# m20048_GPS.net
KiCad netlist of a schematic drawn in Altium Designer
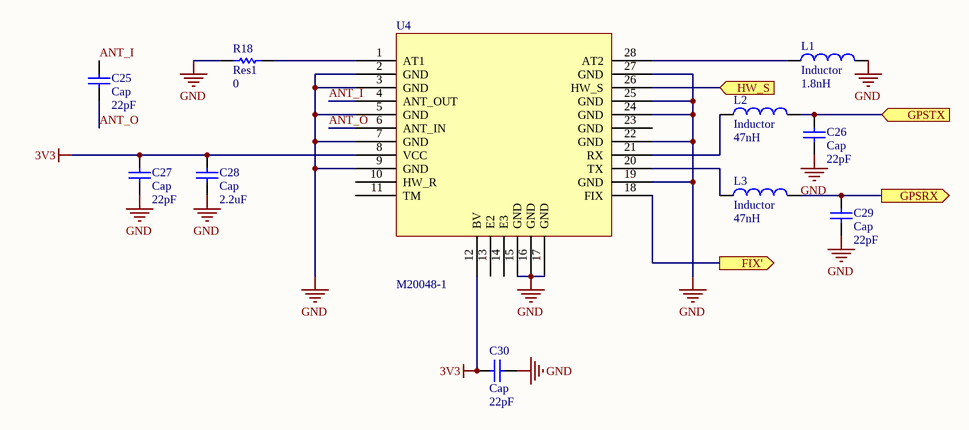
[diagram p0: m20048 GPS.SchDoc]

(export (version "E")
  (design (tool "Eeschema 10.0.6"))
  (components
    (comp (ref "C25")
      (value "Cap")
      (footprint "0402-A")
      (description "Capacitor")
      (fields (field (name "ALTIUM_VALUE") "22pF") (field (name "PUBLISHER") "Altium Limited"))
      (libsource (lib "Miscellaneous Devices") (part "Cap"))
    )
    (comp (ref "C26")
      (value "Cap")
      (footprint "0402-A")
      (description "Capacitor")
      (fields (field (name "ALTIUM_VALUE") "22pF") (field (name "PUBLISHER") "Altium Limited"))
      (libsource (lib "Miscellaneous Devices") (part "Cap"))
    )
    (comp (ref "C27")
      (value "Cap")
      (footprint "0402-A")
      (description "Capacitor")
      (fields (field (name "ALTIUM_VALUE") "22pF") (field (name "PUBLISHER") "Altium Limited"))
      (libsource (lib "Miscellaneous Devices") (part "Cap"))
    )
    (comp (ref "C28")
      (value "Cap")
      (footprint "0402-A")
      (description "Capacitor")
      (fields (field (name "ALTIUM_VALUE") "2.2uF") (field (name "PUBLISHER") "Altium Limited"))
      (libsource (lib "Miscellaneous Devices") (part "Cap"))
    )
    (comp (ref "C29")
      (value "Cap")
      (footprint "0402-A")
      (description "Capacitor")
      (fields (field (name "ALTIUM_VALUE") "22pF") (field (name "PUBLISHER") "Altium Limited"))
      (libsource (lib "Miscellaneous Devices") (part "Cap"))
    )
    (comp (ref "C30")
      (value "Cap")
      (footprint "0402-A")
      (description "Capacitor")
      (fields (field (name "ALTIUM_VALUE") "22pF") (field (name "PUBLISHER") "Altium Limited"))
      (libsource (lib "Miscellaneous Devices") (part "Cap"))
    )
    (comp (ref "L1")
      (value "Inductor")
      (footprint "0402-A")
      (fields (field (name "ALTIUM_VALUE") "1.8nH") (field (name "PUBLISHER") "Altium Limited"))
      (libsource (lib "Miscellaneous Devices") (part "Inductor"))
    )
    (comp (ref "L2")
      (value "Inductor")
      (footprint "0402-A")
      (fields (field (name "ALTIUM_VALUE") "47nH") (field (name "PUBLISHER") "Altium Limited"))
      (libsource (lib "Miscellaneous Devices") (part "Inductor"))
    )
    (comp (ref "L3")
      (value "Inductor")
      (footprint "0402-A")
      (fields (field (name "ALTIUM_VALUE") "47nH") (field (name "PUBLISHER") "Altium Limited"))
      (libsource (lib "Miscellaneous Devices") (part "Inductor"))
    )
    (comp (ref "R18")
      (value "Res1")
      (footprint "0402-A")
      (description "Resistor")
      (fields (field (name "ALTIUM_VALUE") "0") (field (name "PUBLISHER") "Altium Limited"))
      (libsource (lib "Miscellaneous Devices") (part "Res1"))
    )
    (comp (ref "U4") (value "M20048-1") (footprint "M20048-1") (libsource (lib "m20048") (part "M20048-1")))
  )
  (nets
    (net (code "1") (name "/ANT_I") (class "Default")
      (node (ref "C25") (pin "2") (pinfunction "2_2") (pintype "passive"))
      (node (ref "U4") (pin "4") (pinfunction "ANT_OUT_4") (pintype "passive"))
    )
    (net (code "2") (name "/ANT_O") (class "Default")
      (node (ref "C25") (pin "1") (pinfunction "1_1") (pintype "passive"))
      (node (ref "U4") (pin "6") (pinfunction "ANT_IN_6") (pintype "passive"))
    )
    (net (code "3") (name "/FIX'") (class "Default")
      (node (ref "U4") (pin "18") (pinfunction "FIX_18") (pintype "passive"))
    )
    (net (code "4") (name "/GPSRX") (class "Default")
      (node (ref "C29") (pin "2") (pinfunction "2_2") (pintype "passive"))
      (node (ref "L3") (pin "2") (pinfunction "2_2") (pintype "passive"))
    )
    (net (code "5") (name "/GPSTX") (class "Default")
      (node (ref "C26") (pin "2") (pinfunction "2_2") (pintype "passive"))
      (node (ref "L2") (pin "2") (pinfunction "2_2") (pintype "passive"))
    )
    (net (code "6") (name "/HW_S") (class "Default")
      (node (ref "U4") (pin "26") (pinfunction "HW_S_26") (pintype "passive"))
    )
    (net (code "7") (name "3V3") (class "Default")
      (node (ref "C27") (pin "2") (pinfunction "2_2") (pintype "passive"))
      (node (ref "C28") (pin "2") (pinfunction "2_2") (pintype "passive"))
      (node (ref "C30") (pin "2") (pinfunction "2_2") (pintype "passive"))
      (node (ref "U4") (pin "12") (pinfunction "BV_12") (pintype "passive"))
      (node (ref "U4") (pin "8") (pinfunction "VCC_8") (pintype "passive"))
    )
    (net (code "8") (name "GND") (class "Default")
      (node (ref "C26") (pin "1") (pinfunction "1_1") (pintype "passive"))
      (node (ref "C27") (pin "1") (pinfunction "1_1") (pintype "passive"))
      (node (ref "C28") (pin "1") (pinfunction "1_1") (pintype "passive"))
      (node (ref "C29") (pin "1") (pinfunction "1_1") (pintype "passive"))
      (node (ref "C30") (pin "1") (pinfunction "1_1") (pintype "passive"))
      (node (ref "L1") (pin "2") (pinfunction "2_2") (pintype "passive"))
      (node (ref "R18") (pin "1") (pinfunction "1_1") (pintype "passive"))
      (node (ref "U4") (pin "15") (pinfunction "GND_15") (pintype "passive"))
      (node (ref "U4") (pin "16") (pinfunction "GND_16") (pintype "passive"))
      (node (ref "U4") (pin "17") (pinfunction "GND_17") (pintype "passive"))
      (node (ref "U4") (pin "19") (pinfunction "GND_19") (pintype "passive"))
      (node (ref "U4") (pin "2") (pinfunction "GND_2") (pintype "passive"))
      (node (ref "U4") (pin "22") (pinfunction "GND_22") (pintype "passive"))
      (node (ref "U4") (pin "24") (pinfunction "GND_24") (pintype "passive"))
      (node (ref "U4") (pin "25") (pinfunction "GND_25") (pintype "passive"))
      (node (ref "U4") (pin "27") (pinfunction "GND_27") (pintype "passive"))
      (node (ref "U4") (pin "3") (pinfunction "GND_3") (pintype "passive"))
      (node (ref "U4") (pin "5") (pinfunction "GND_5") (pintype "passive"))
      (node (ref "U4") (pin "7") (pinfunction "GND_7") (pintype "passive"))
      (node (ref "U4") (pin "9") (pinfunction "GND_9") (pintype "passive"))
    )
    (net (code "9") (name "Net-(U4-AT1)") (class "Default")
      (node (ref "R18") (pin "2") (pinfunction "2_2") (pintype "passive"))
      (node (ref "U4") (pin "1") (pinfunction "AT1_1") (pintype "passive"))
    )
    (net (code "10") (name "Net-(U4-AT2)") (class "Default")
      (node (ref "L1") (pin "1") (pinfunction "1_1") (pintype "passive"))
      (node (ref "U4") (pin "28") (pinfunction "AT2_28") (pintype "passive"))
    )
    (net (code "11") (name "Net-(U4-RX)") (class "Default")
      (node (ref "L2") (pin "1") (pinfunction "1_1") (pintype "passive"))
      (node (ref "U4") (pin "21") (pinfunction "RX_21") (pintype "passive"))
    )
    (net (code "12") (name "Net-(U4-TX)") (class "Default")
      (node (ref "L3") (pin "1") (pinfunction "1_1") (pintype "passive"))
      (node (ref "U4") (pin "20") (pinfunction "TX_20") (pintype "passive"))
    )
    (net (code "13") (name "unconnected-(U4-E2-Pad13)") (class "Default")
      (node (ref "U4") (pin "13") (pinfunction "E2_13") (pintype "passive"))
    )
    (net (code "14") (name "unconnected-(U4-E3-Pad14)") (class "Default")
      (node (ref "U4") (pin "14") (pinfunction "E3_14") (pintype "passive"))
    )
    (net (code "15") (name "unconnected-(U4-GND-Pad23)") (class "Default")
      (node (ref "U4") (pin "23") (pinfunction "GND_23") (pintype "passive"))
    )
    (net (code "16") (name "unconnected-(U4-HW_R-Pad10)") (class "Default")
      (node (ref "U4") (pin "10") (pinfunction "HW_R_10") (pintype "passive"))
    )
    (net (code "17") (name "unconnected-(U4-TM-Pad11)") (class "Default")
      (node (ref "U4") (pin "11") (pinfunction "TM_11") (pintype "passive"))
    )
  )
)
